# TopSheet.net
KiCad netlist of a schematic drawn in Altium Designer
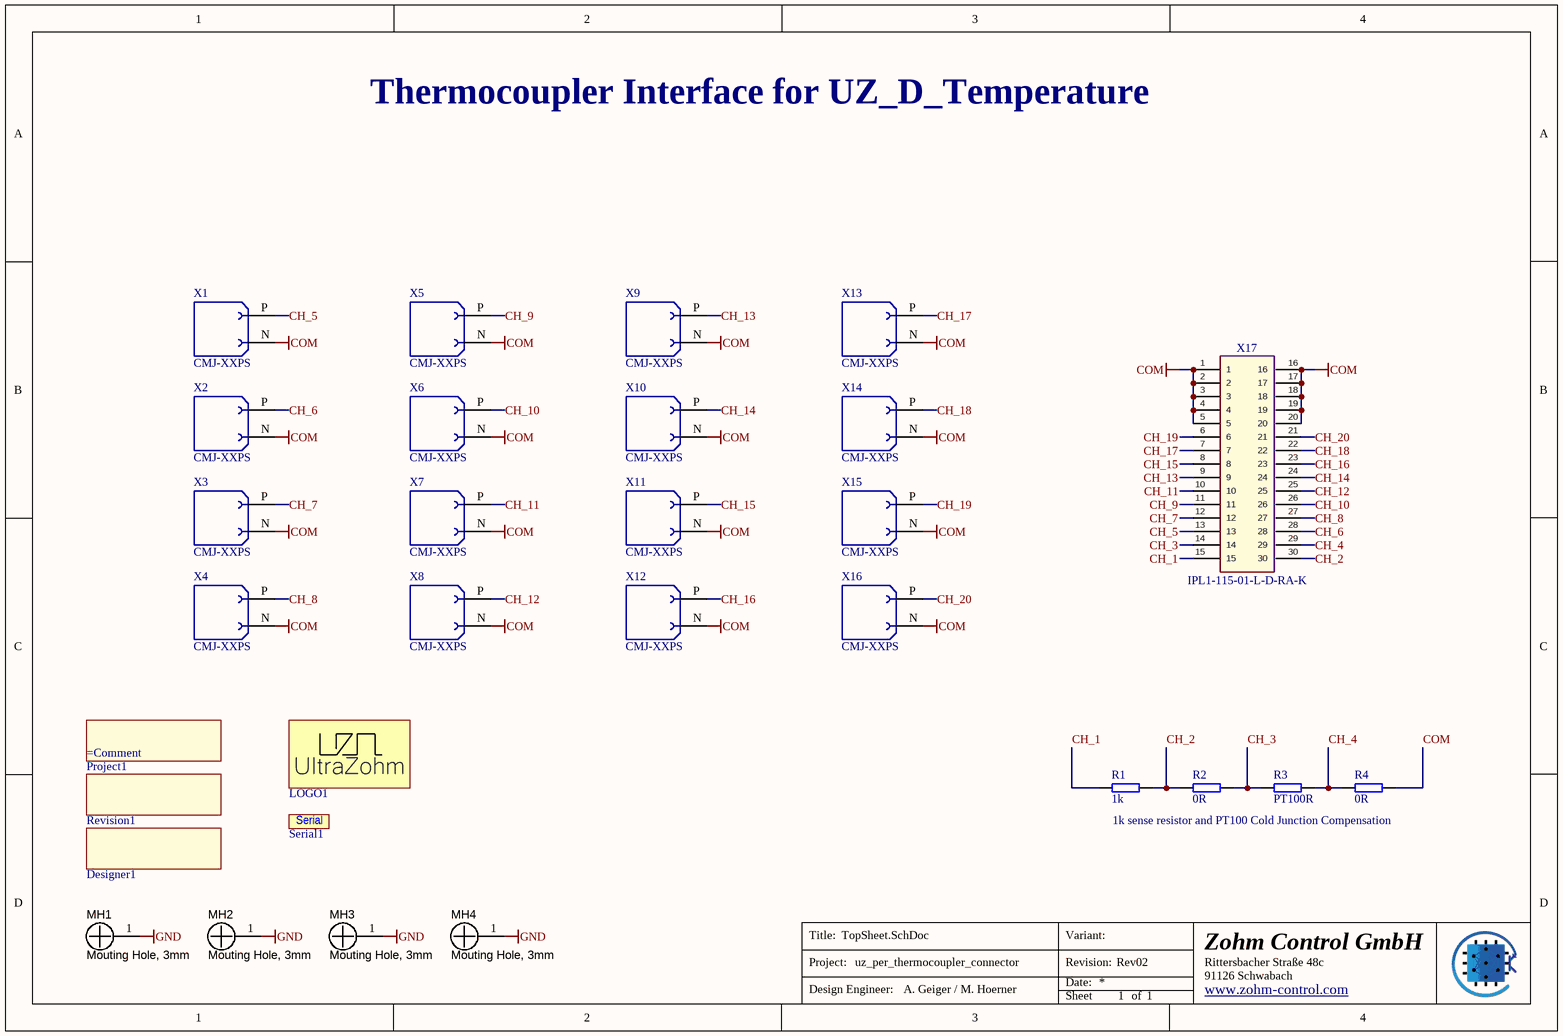
[diagram p0: TopSheet.SchDoc]

(export (version "E")
  (design (tool "Eeschema 10.0.6"))
  (components
    (comp (ref "Designer1")
      (value "~")
      (footprint "Designator:comment")
      (fields
        (field (name "MANUFACTURER") "PCB Manufacturer")
        (field (name "MANUFACTURER PART NUMBER") "Project Author")
        (field (name "CREATED FROM") "T. Wendt")
      )
      (libsource (lib "user") (part "ProjectAuthor"))
    )
    (comp (ref "LOGO1")
      (value "UZ Logo")
      (footprint "UZ_Logo_medium")
      (description "Official Project Logo of the UltraZohm")
      (fields
        (field (name "MANUFACTURER") "PCB Manufacturer")
        (field (name "MANUFACTURER PART NUMBER") "UltraZohm Logo")
        (field (name "CREATED FROM") "T. Wendt")
      )
      (libsource (lib "user") (part "UZ_LOGO"))
    )
    (comp (ref "MH1")
      (value "Mouting Hole, 3mm")
      (footprint "NY PMS 440 0025 PH")
      (description "Machine Screw, Round, #4-40 x 1/4, Nylon, Philips panhead")
      (fields
        (field (name "MF") "B&F Fastener Supply")
        (field (name "MPN") "NY PMS 440 0025 PH")
        (field (name "CREATED") "2021_06_22_AGeiger")
      )
      (libsource (lib "ZC_Lib") (part "NY PMS 440 0025 PH"))
    )
    (comp (ref "MH2")
      (value "Mouting Hole, 3mm")
      (footprint "NY PMS 440 0025 PH")
      (description "Machine Screw, Round, #4-40 x 1/4, Nylon, Philips panhead")
      (fields
        (field (name "MF") "B&F Fastener Supply")
        (field (name "MPN") "NY PMS 440 0025 PH")
        (field (name "CREATED") "2021_06_22_AGeiger")
      )
      (libsource (lib "ZC_Lib") (part "NY PMS 440 0025 PH"))
    )
    (comp (ref "MH3")
      (value "Mouting Hole, 3mm")
      (footprint "NY PMS 440 0025 PH")
      (description "Machine Screw, Round, #4-40 x 1/4, Nylon, Philips panhead")
      (fields
        (field (name "MF") "B&F Fastener Supply")
        (field (name "MPN") "NY PMS 440 0025 PH")
        (field (name "CREATED") "2021_06_22_AGeiger")
      )
      (libsource (lib "ZC_Lib") (part "NY PMS 440 0025 PH"))
    )
    (comp (ref "MH4")
      (value "Mouting Hole, 3mm")
      (footprint "NY PMS 440 0025 PH")
      (description "Machine Screw, Round, #4-40 x 1/4, Nylon, Philips panhead")
      (fields
        (field (name "MF") "B&F Fastener Supply")
        (field (name "MPN") "NY PMS 440 0025 PH")
        (field (name "CREATED") "2021_06_22_AGeiger")
      )
      (libsource (lib "ZC_Lib") (part "NY PMS 440 0025 PH"))
    )
    (comp (ref "Project1")
      (value "~")
      (footprint "COMMENT")
      (fields
        (field (name "MANUFACTURER") "PCB Manufacturer")
        (field (name "MANUFACTURER PART NUMBER") "Project Name")
        (field (name "CREATED FROM") "T. Wendt")
      )
      (libsource (lib "user") (part "ProjectName"))
    )
    (comp (ref "R1")
      (value "1k")
      (footprint "RES 0603_1608")
      (description "100mW ±0.1% ±25ppm/℃ 1kΩ 0603 Chip Resistor - Surface Mount ROHS")
      (fields
        (field (name "MANUFACTURER PART NUMBER") "AR03BTCX1001")
        (field (name "MANUFACTURER") "Viking Tech")
        (field (name "CREATED FROM") "AGeiger")
      )
      (libsource (lib "user") (part "Resistor"))
    )
    (comp (ref "R2")
      (value "0R")
      (footprint "RES 0603_1608")
      (description "SMD resistor E24 series")
      (fields
        (field (name "MANUFACTURER PART NUMBER") "RC0603JR-070RL")
        (field (name "MANUFACTURER") "YAGEO")
        (field (name "CREATED FROM") "MGremer")
      )
      (libsource (lib "user") (part "Resistor"))
    )
    (comp (ref "R3")
      (value "PT100R")
      (footprint "RES 0603_1608")
      (description "SMD resistor PT100")
      (fields
        (field (name "MANUFACTURER PART NUMBER") "PTS060301B100RPU00")
        (field (name "MANUFACTURER") "Vishay")
        (field (name "CREATED FROM") "MHoerner")
      )
      (libsource (lib "user") (part "Resistor"))
    )
    (comp (ref "R4")
      (value "0R")
      (footprint "RES 0603_1608")
      (description "SMD resistor E24 series")
      (fields
        (field (name "MANUFACTURER PART NUMBER") "RC0603JR-070RL")
        (field (name "MANUFACTURER") "YAGEO")
        (field (name "CREATED FROM") "MGremer")
      )
      (libsource (lib "user") (part "Resistor"))
    )
    (comp (ref "Revision1")
      (value "~")
      (footprint "Designator:comment")
      (fields
        (field (name "MANUFACTURER") "PCB Manufacturer")
        (field (name "MANUFACTURER PART NUMBER") "Project Revision")
        (field (name "CREATED FROM") "T. Wendt")
      )
      (libsource (lib "user") (part "ProjectRevision"))
    )
    (comp (ref "Serial1")
      (value "Serial #")
      (footprint "SERIAL")
      (description "Field to put in a serial number")
      (fields
        (field (name "MANUFACTURER") "PCB Manufacturer")
        (field (name "MANUFACTURER PART NUMBER") "Serial Number")
        (field (name "CREATED FROM") "T. Wendt")
      )
      (libsource (lib "user") (part "SerialNumber"))
    )
    (comp (ref "X1")
      (value "CMJ-XXPS")
      (footprint "CMJ-XXPS")
      (description "Connector Miniature Jack PCB Side Mounting")
      (libsource (lib "user") (part "CMJ-XXPS"))
    )
    (comp (ref "X2")
      (value "CMJ-XXPS")
      (footprint "CMJ-XXPS")
      (description "Connector Miniature Jack PCB Side Mounting")
      (libsource (lib "user") (part "CMJ-XXPS"))
    )
    (comp (ref "X3")
      (value "CMJ-XXPS")
      (footprint "CMJ-XXPS")
      (description "Connector Miniature Jack PCB Side Mounting")
      (libsource (lib "user") (part "CMJ-XXPS"))
    )
    (comp (ref "X4")
      (value "CMJ-XXPS")
      (footprint "CMJ-XXPS")
      (description "Connector Miniature Jack PCB Side Mounting")
      (libsource (lib "user") (part "CMJ-XXPS"))
    )
    (comp (ref "X5")
      (value "CMJ-XXPS")
      (footprint "CMJ-XXPS")
      (description "Connector Miniature Jack PCB Side Mounting")
      (libsource (lib "user") (part "CMJ-XXPS"))
    )
    (comp (ref "X6")
      (value "CMJ-XXPS")
      (footprint "CMJ-XXPS")
      (description "Connector Miniature Jack PCB Side Mounting")
      (libsource (lib "user") (part "CMJ-XXPS"))
    )
    (comp (ref "X7")
      (value "CMJ-XXPS")
      (footprint "CMJ-XXPS")
      (description "Connector Miniature Jack PCB Side Mounting")
      (libsource (lib "user") (part "CMJ-XXPS"))
    )
    (comp (ref "X8")
      (value "CMJ-XXPS")
      (footprint "CMJ-XXPS")
      (description "Connector Miniature Jack PCB Side Mounting")
      (libsource (lib "user") (part "CMJ-XXPS"))
    )
    (comp (ref "X9")
      (value "CMJ-XXPS")
      (footprint "CMJ-XXPS")
      (description "Connector Miniature Jack PCB Side Mounting")
      (libsource (lib "user") (part "CMJ-XXPS"))
    )
    (comp (ref "X10")
      (value "CMJ-XXPS")
      (footprint "CMJ-XXPS")
      (description "Connector Miniature Jack PCB Side Mounting")
      (libsource (lib "user") (part "CMJ-XXPS"))
    )
    (comp (ref "X11")
      (value "CMJ-XXPS")
      (footprint "CMJ-XXPS")
      (description "Connector Miniature Jack PCB Side Mounting")
      (libsource (lib "user") (part "CMJ-XXPS"))
    )
    (comp (ref "X12")
      (value "CMJ-XXPS")
      (footprint "CMJ-XXPS")
      (description "Connector Miniature Jack PCB Side Mounting")
      (libsource (lib "user") (part "CMJ-XXPS"))
    )
    (comp (ref "X13")
      (value "CMJ-XXPS")
      (footprint "CMJ-XXPS")
      (description "Connector Miniature Jack PCB Side Mounting")
      (libsource (lib "user") (part "CMJ-XXPS"))
    )
    (comp (ref "X14")
      (value "CMJ-XXPS")
      (footprint "CMJ-XXPS")
      (description "Connector Miniature Jack PCB Side Mounting")
      (libsource (lib "user") (part "CMJ-XXPS"))
    )
    (comp (ref "X15")
      (value "CMJ-XXPS")
      (footprint "CMJ-XXPS")
      (description "Connector Miniature Jack PCB Side Mounting")
      (libsource (lib "user") (part "CMJ-XXPS"))
    )
    (comp (ref "X16")
      (value "CMJ-XXPS")
      (footprint "CMJ-XXPS")
      (description "Connector Miniature Jack PCB Side Mounting")
      (libsource (lib "user") (part "CMJ-XXPS"))
    )
    (comp (ref "X17")
      (value "IPL1-115-01-L-D-RA-K")
      (footprint "IPL1-115-01-XX-D-RA")
      (description "Terminal Assembly, Double Row, Right Angle, Thru-Hole, 2.54 mm x 2.54 mm Pitch, 30 Pins")
      (fields
        (field (name "MANUFACTURER") "SAMTEC")
        (field (name "LCSC PART NUMBER") "C7423882")
        (field (name "CREATED FROM") "TWendt")
      )
      (libsource (lib "user") (part "IPL1-115-01-XX-D-XX"))
    )
  )
  (nets
    (net (code "1") (name "/CH_1") (class "Default")
      (node (ref "R1") (pin "1") (pinfunction "1_1") (pintype "passive"))
      (node (ref "X17") (pin "15") (pinfunction "15_15") (pintype "passive"))
    )
    (net (code "2") (name "/CH_2") (class "Default")
      (node (ref "R1") (pin "2") (pinfunction "2_2") (pintype "passive"))
      (node (ref "R2") (pin "1") (pinfunction "1_1") (pintype "passive"))
      (node (ref "X17") (pin "30") (pinfunction "30_30") (pintype "passive"))
    )
    (net (code "3") (name "/CH_3") (class "Default")
      (node (ref "R2") (pin "2") (pinfunction "2_2") (pintype "passive"))
      (node (ref "R3") (pin "1") (pinfunction "1_1") (pintype "passive"))
      (node (ref "X17") (pin "14") (pinfunction "14_14") (pintype "passive"))
    )
    (net (code "4") (name "/CH_4") (class "Default")
      (node (ref "R3") (pin "2") (pinfunction "2_2") (pintype "passive"))
      (node (ref "R4") (pin "1") (pinfunction "1_1") (pintype "passive"))
      (node (ref "X17") (pin "29") (pinfunction "29_29") (pintype "passive"))
    )
    (net (code "5") (name "/CH_5") (class "Default")
      (node (ref "X1") (pin "P") (pinfunction "POS_P") (pintype "passive"))
      (node (ref "X17") (pin "13") (pinfunction "13_13") (pintype "passive"))
    )
    (net (code "6") (name "/CH_6") (class "Default")
      (node (ref "X17") (pin "28") (pinfunction "28_28") (pintype "passive"))
      (node (ref "X2") (pin "P") (pinfunction "POS_P") (pintype "passive"))
    )
    (net (code "7") (name "/CH_7") (class "Default")
      (node (ref "X17") (pin "12") (pinfunction "12_12") (pintype "passive"))
      (node (ref "X3") (pin "P") (pinfunction "POS_P") (pintype "passive"))
    )
    (net (code "8") (name "/CH_8") (class "Default")
      (node (ref "X17") (pin "27") (pinfunction "27_27") (pintype "passive"))
      (node (ref "X4") (pin "P") (pinfunction "POS_P") (pintype "passive"))
    )
    (net (code "9") (name "/CH_9") (class "Default")
      (node (ref "X17") (pin "11") (pinfunction "11_11") (pintype "passive"))
      (node (ref "X5") (pin "P") (pinfunction "POS_P") (pintype "passive"))
    )
    (net (code "10") (name "/CH_10") (class "Default")
      (node (ref "X17") (pin "26") (pinfunction "26_26") (pintype "passive"))
      (node (ref "X6") (pin "P") (pinfunction "POS_P") (pintype "passive"))
    )
    (net (code "11") (name "/CH_11") (class "Default")
      (node (ref "X17") (pin "10") (pinfunction "10_10") (pintype "passive"))
      (node (ref "X7") (pin "P") (pinfunction "POS_P") (pintype "passive"))
    )
    (net (code "12") (name "/CH_12") (class "Default")
      (node (ref "X17") (pin "25") (pinfunction "25_25") (pintype "passive"))
      (node (ref "X8") (pin "P") (pinfunction "POS_P") (pintype "passive"))
    )
    (net (code "13") (name "/CH_13") (class "Default")
      (node (ref "X17") (pin "9") (pinfunction "9_9") (pintype "passive"))
      (node (ref "X9") (pin "P") (pinfunction "POS_P") (pintype "passive"))
    )
    (net (code "14") (name "/CH_14") (class "Default")
      (node (ref "X10") (pin "P") (pinfunction "POS_P") (pintype "passive"))
      (node (ref "X17") (pin "24") (pinfunction "24_24") (pintype "passive"))
    )
    (net (code "15") (name "/CH_15") (class "Default")
      (node (ref "X11") (pin "P") (pinfunction "POS_P") (pintype "passive"))
      (node (ref "X17") (pin "8") (pinfunction "8_8") (pintype "passive"))
    )
    (net (code "16") (name "/CH_16") (class "Default")
      (node (ref "X12") (pin "P") (pinfunction "POS_P") (pintype "passive"))
      (node (ref "X17") (pin "23") (pinfunction "23_23") (pintype "passive"))
    )
    (net (code "17") (name "/CH_17") (class "Default")
      (node (ref "X13") (pin "P") (pinfunction "POS_P") (pintype "passive"))
      (node (ref "X17") (pin "7") (pinfunction "7_7") (pintype "passive"))
    )
    (net (code "18") (name "/CH_18") (class "Default")
      (node (ref "X14") (pin "P") (pinfunction "POS_P") (pintype "passive"))
      (node (ref "X17") (pin "22") (pinfunction "22_22") (pintype "passive"))
    )
    (net (code "19") (name "/CH_19") (class "Default")
      (node (ref "X15") (pin "P") (pinfunction "POS_P") (pintype "passive"))
      (node (ref "X17") (pin "6") (pinfunction "6_6") (pintype "passive"))
    )
    (net (code "20") (name "/CH_20") (class "Default")
      (node (ref "X16") (pin "P") (pinfunction "POS_P") (pintype "passive"))
      (node (ref "X17") (pin "21") (pinfunction "21_21") (pintype "passive"))
    )
    (net (code "21") (name "COM") (class "Default")
      (node (ref "R4") (pin "2") (pinfunction "2_2") (pintype "passive"))
      (node (ref "X1") (pin "N") (pinfunction "NEG_N") (pintype "passive"))
      (node (ref "X10") (pin "N") (pinfunction "NEG_N") (pintype "passive"))
      (node (ref "X11") (pin "N") (pinfunction "NEG_N") (pintype "passive"))
      (node (ref "X12") (pin "N") (pinfunction "NEG_N") (pintype "passive"))
      (node (ref "X13") (pin "N") (pinfunction "NEG_N") (pintype "passive"))
      (node (ref "X14") (pin "N") (pinfunction "NEG_N") (pintype "passive"))
      (node (ref "X15") (pin "N") (pinfunction "NEG_N") (pintype "passive"))
      (node (ref "X16") (pin "N") (pinfunction "NEG_N") (pintype "passive"))
      (node (ref "X17") (pin "1") (pinfunction "1_1") (pintype "passive"))
      (node (ref "X17") (pin "16") (pinfunction "16_16") (pintype "passive"))
      (node (ref "X17") (pin "17") (pinfunction "17_17") (pintype "passive"))
      (node (ref "X17") (pin "18") (pinfunction "18_18") (pintype "passive"))
      (node (ref "X17") (pin "19") (pinfunction "19_19") (pintype "passive"))
      (node (ref "X17") (pin "2") (pinfunction "2_2") (pintype "passive"))
      (node (ref "X17") (pin "20") (pinfunction "20_20") (pintype "passive"))
      (node (ref "X17") (pin "3") (pinfunction "3_3") (pintype "passive"))
      (node (ref "X17") (pin "4") (pinfunction "4_4") (pintype "passive"))
      (node (ref "X17") (pin "5") (pinfunction "5_5") (pintype "passive"))
      (node (ref "X2") (pin "N") (pinfunction "NEG_N") (pintype "passive"))
      (node (ref "X3") (pin "N") (pinfunction "NEG_N") (pintype "passive"))
      (node (ref "X4") (pin "N") (pinfunction "NEG_N") (pintype "passive"))
      (node (ref "X5") (pin "N") (pinfunction "NEG_N") (pintype "passive"))
      (node (ref "X6") (pin "N") (pinfunction "NEG_N") (pintype "passive"))
      (node (ref "X7") (pin "N") (pinfunction "NEG_N") (pintype "passive"))
      (node (ref "X8") (pin "N") (pinfunction "NEG_N") (pintype "passive"))
      (node (ref "X9") (pin "N") (pinfunction "NEG_N") (pintype "passive"))
    )
    (net (code "22") (name "GND") (class "Default")
      (node (ref "MH1") (pin "1") (pinfunction "1_1") (pintype "passive"))
      (node (ref "MH2") (pin "1") (pinfunction "1_1") (pintype "passive"))
      (node (ref "MH3") (pin "1") (pinfunction "1_1") (pintype "passive"))
      (node (ref "MH4") (pin "1") (pinfunction "1_1") (pintype "passive"))
    )
  )
)
